# BOARD1_V2.net
KiCad netlist of a schematic drawn in Altium Designer
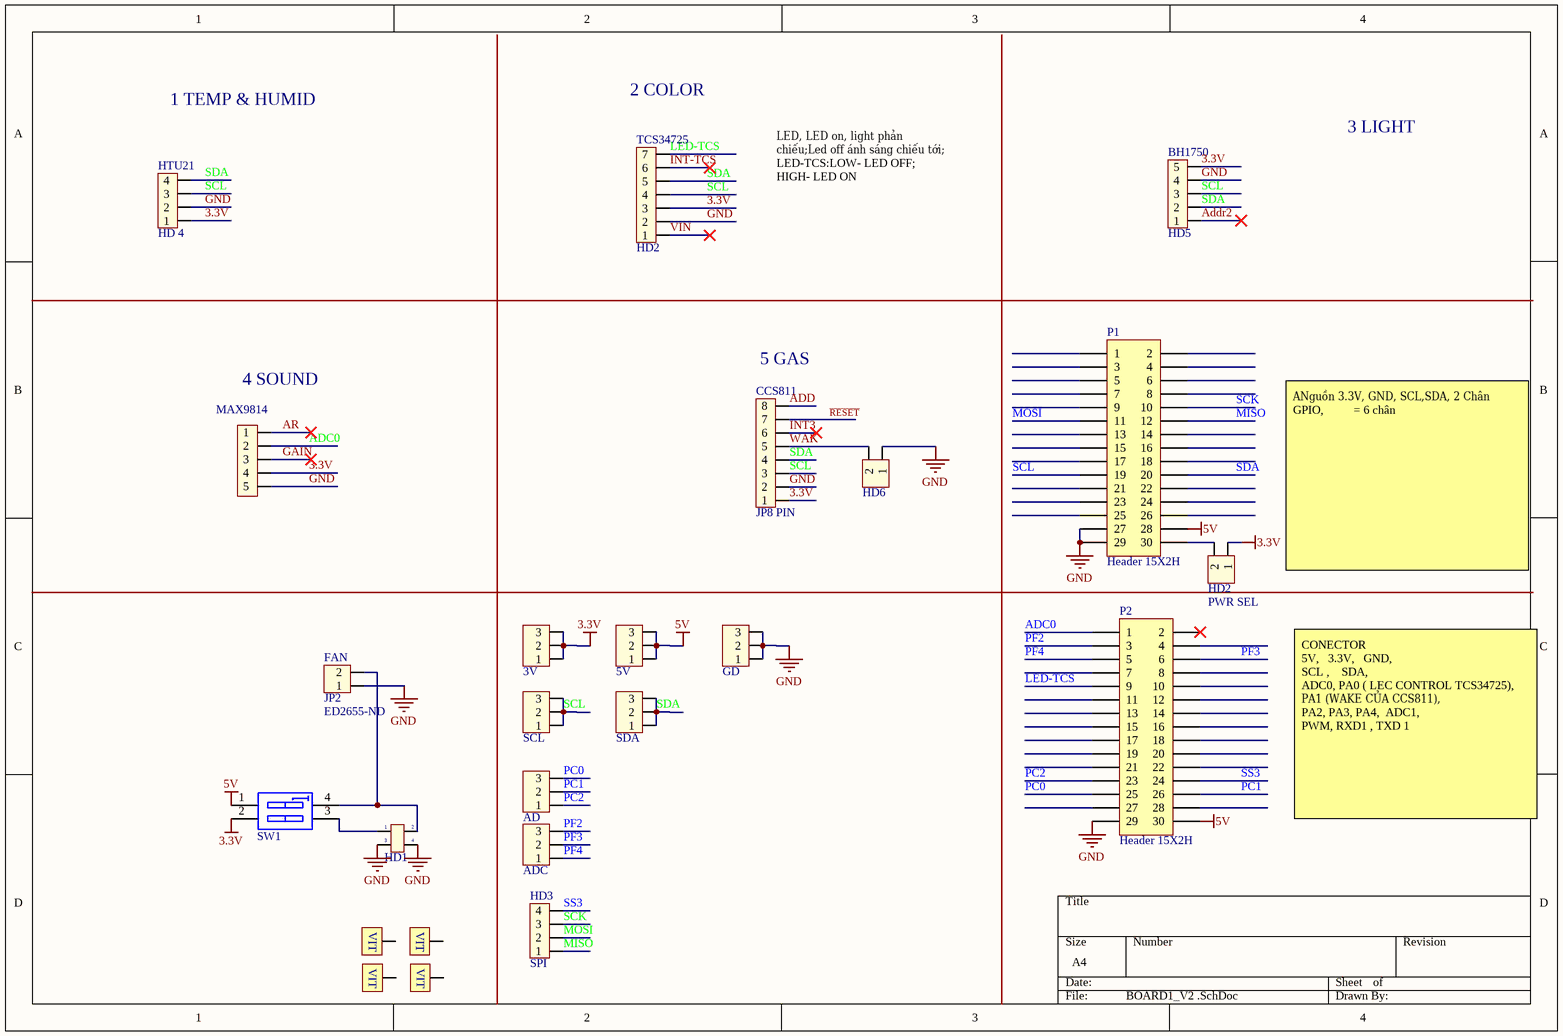
[diagram p0: BOARD1_V2 .SchDoc]

(export (version "E")
  (design (tool "Eeschema 10.0.6"))
  (components
    (comp (ref "3V") (value "Header 3") (footprint "Header_3") (libsource (lib "lpson") (part "Header3")))
    (comp (ref "5V") (value "Header 3") (footprint "Header_3") (libsource (lib "lpson") (part "Header3")))
    (comp (ref "AD") (value "Header 3") (footprint "Header_3") (libsource (lib "lpson") (part "Header3")))
    (comp (ref "ADC") (value "Header 3") (footprint "Header_3") (libsource (lib "lpson") (part "Header3")))
    (comp (ref "BH1750")
      (value "HD5")
      (footprint "BH1750")
      (description "Header 5")
      (fields (field (name "CREAT BY") "VanDungEvn@Gmail.com"))
      (libsource (lib "lpson") (part "Header5"))
    )
    (comp (ref "CCS811") (value "JP8 PIN") (footprint "CCS811V2") (libsource (lib "lpson") (part "JP8")))
    (comp (ref "FAN")
      (value "JP2")
      (footprint "CON2")
      (description "Terminal 2pin 5mm")
      (fields
        (field (name "MANUFACTURER") "On Shore Technology Inc.")
        (field (name "MANUFACTURER PART NUMBER") "OSTTH020160")
        (field (name "SUPPLIER PART NUMBER 1") "ED2655-ND")
      )
      (libsource (lib "lpson") (part "Terminal 2"))
    )
    (comp (ref "GD") (value "Header 3") (footprint "Header_3") (libsource (lib "lpson") (part "Header3")))
    (comp (ref "HD1") (value "Jumper 2x2") (footprint "HDR2X2") (libsource (lib "lpson") (part "JP2x2")))
    (comp (ref "HD2")
      (value "PWR SEL")
      (footprint "Header_2")
      (description "Header 2")
      (libsource (lib "lpson") (part "Header2"))
    )
    (comp (ref "HD3")
      (value "SPI")
      (footprint "Header_4")
      (description "Header 4")
      (libsource (lib "lpson") (part "Header4"))
    )
    (comp (ref "HD6")
      (value "PWR SEL")
      (footprint "Header_2")
      (description "Header 2")
      (libsource (lib "lpson") (part "Header2"))
    )
    (comp (ref "HTU21")
      (value "HD 4")
      (footprint "HTU-D")
      (description "Header 4")
      (libsource (lib "lpson") (part "Header4"))
    )
    (comp (ref "MAX9814")
      (value "JP5")
      (footprint "MAX9814")
      (libsource (lib "quangnguyen_lib_altium") (part "JP5"))
    )
    (comp (ref "P1")
      (value "Header 15X2H")
      (footprint "HED15X2H")
      (description "Header, 15-Pin, Dual row, Right Angle")
      (fields (field (name "PUBLISHER") "Altium Limited"))
      (libsource (lib "My Library") (part "Header 15X2H"))
    )
    (comp (ref "P2")
      (value "Header 15X2H")
      (footprint "HED15X2H")
      (description "Header, 15-Pin, Dual row, Right Angle")
      (fields (field (name "PUBLISHER") "Altium Limited"))
      (libsource (lib "My Library") (part "Header 15X2H"))
    )
    (comp (ref "SCL") (value "Header 3") (footprint "Header_3") (libsource (lib "lpson") (part "Header3")))
    (comp (ref "SDA") (value "Header 3") (footprint "Header_3") (libsource (lib "lpson") (part "Header3")))
    (comp (ref "SW1")
      (value "SW - DIP2")
      (footprint "DIP_Switch2")
      (description "DIP Switch, 2 Position, SPST")
      (libsource (lib "lpson") (part "SWDIP-2"))
    )
    (comp (ref "TCS34725")
      (value "HD2")
      (footprint "TCS34725V2")
      (description "JP7 PIN")
      (libsource (lib "lpson") (part "JP7"))
    )
    (comp (ref "VIT2")
      (value "1")
      (footprint "Screw 3 small")
      (description "Oc Vit")
      (libsource (lib "quangnguyen_lib_altium") (part "VIT"))
    )
    (comp (ref "VIT3")
      (value "1")
      (footprint "Screw 3 small")
      (description "Oc Vit")
      (libsource (lib "quangnguyen_lib_altium") (part "VIT"))
    )
    (comp (ref "VIT5")
      (value "1")
      (footprint "Screw 3 small")
      (description "Oc Vit")
      (libsource (lib "quangnguyen_lib_altium") (part "VIT"))
    )
    (comp (ref "VIT6")
      (value "1")
      (footprint "Screw 3 small")
      (description "Oc Vit")
      (libsource (lib "quangnguyen_lib_altium") (part "VIT"))
    )
  )
  (nets
    (net (code "1") (name "/ADC0") (class "Default")
      (node (ref "MAX9814") (pin "2") (pinfunction "2_2") (pintype "passive"))
      (node (ref "P2") (pin "1") (pinfunction "1_1") (pintype "passive"))
    )
    (net (code "2") (name "/ADD") (class "Default")
      (node (ref "CCS811") (pin "8") (pinfunction "8_8") (pintype "passive"))
    )
    (net (code "3") (name "/AR") (class "Default")
      (node (ref "MAX9814") (pin "1") (pinfunction "1_1") (pintype "passive+no_connect"))
    )
    (net (code "4") (name "/Addr2") (class "Default")
      (node (ref "BH1750") (pin "1") (pinfunction "1_1") (pintype "passive+no_connect"))
    )
    (net (code "5") (name "/GAIN") (class "Default")
      (node (ref "MAX9814") (pin "3") (pinfunction "3_3") (pintype "passive+no_connect"))
    )
    (net (code "6") (name "/INT-TCS") (class "Default")
      (node (ref "TCS34725") (pin "6") (pinfunction "6_6") (pintype "passive+no_connect"))
    )
    (net (code "7") (name "/INT3") (class "Default")
      (node (ref "CCS811") (pin "6") (pinfunction "6_6") (pintype "passive+no_connect"))
    )
    (net (code "8") (name "/LED-TCS") (class "Default")
      (node (ref "P2") (pin "9") (pinfunction "9_9") (pintype "passive"))
      (node (ref "TCS34725") (pin "7") (pinfunction "7_7") (pintype "passive"))
    )
    (net (code "9") (name "/MISO") (class "Default")
      (node (ref "HD3") (pin "1") (pinfunction "1_1") (pintype "passive"))
      (node (ref "P1") (pin "12") (pinfunction "12_12") (pintype "passive"))
    )
    (net (code "10") (name "/MOSI") (class "Default")
      (node (ref "HD3") (pin "2") (pinfunction "2_2") (pintype "passive"))
      (node (ref "P1") (pin "11") (pinfunction "11_11") (pintype "passive"))
    )
    (net (code "11") (name "/PC0") (class "Default")
      (node (ref "AD") (pin "3") (pinfunction "3_3") (pintype "passive"))
      (node (ref "P2") (pin "25") (pinfunction "25_25") (pintype "passive"))
    )
    (net (code "12") (name "/PC1") (class "Default")
      (node (ref "AD") (pin "2") (pinfunction "2_2") (pintype "passive"))
      (node (ref "P2") (pin "26") (pinfunction "26_26") (pintype "passive"))
    )
    (net (code "13") (name "/PC2") (class "Default")
      (node (ref "AD") (pin "1") (pinfunction "1_1") (pintype "passive"))
      (node (ref "P2") (pin "23") (pinfunction "23_23") (pintype "passive"))
    )
    (net (code "14") (name "/PF2") (class "Default")
      (node (ref "ADC") (pin "3") (pinfunction "3_3") (pintype "passive"))
      (node (ref "P2") (pin "3") (pinfunction "3_3") (pintype "passive"))
    )
    (net (code "15") (name "/PF3") (class "Default")
      (node (ref "ADC") (pin "2") (pinfunction "2_2") (pintype "passive"))
      (node (ref "P2") (pin "6") (pinfunction "6_6") (pintype "passive"))
    )
    (net (code "16") (name "/PF4") (class "Default")
      (node (ref "ADC") (pin "1") (pinfunction "1_1") (pintype "passive"))
      (node (ref "P2") (pin "5") (pinfunction "5_5") (pintype "passive"))
    )
    (net (code "17") (name "/SCK") (class "Default")
      (node (ref "HD3") (pin "3") (pinfunction "3_3") (pintype "passive"))
      (node (ref "P1") (pin "10") (pinfunction "10_10") (pintype "passive"))
    )
    (net (code "18") (name "/SCL") (class "Default")
      (node (ref "BH1750") (pin "3") (pinfunction "3_3") (pintype "passive"))
      (node (ref "CCS811") (pin "3") (pinfunction "3_3") (pintype "passive"))
      (node (ref "HTU21") (pin "3") (pinfunction "3_3") (pintype "passive"))
      (node (ref "P1") (pin "19") (pinfunction "19_19") (pintype "passive"))
      (node (ref "SCL") (pin "1") (pinfunction "1_1") (pintype "passive"))
      (node (ref "SCL") (pin "2") (pinfunction "2_2") (pintype "passive"))
      (node (ref "SCL") (pin "3") (pinfunction "3_3") (pintype "passive"))
      (node (ref "TCS34725") (pin "4") (pinfunction "4_4") (pintype "passive"))
    )
    (net (code "19") (name "/SDA") (class "Default")
      (node (ref "BH1750") (pin "2") (pinfunction "2_2") (pintype "passive"))
      (node (ref "CCS811") (pin "4") (pinfunction "4_4") (pintype "passive"))
      (node (ref "HTU21") (pin "4") (pinfunction "4_4") (pintype "passive"))
      (node (ref "P1") (pin "20") (pinfunction "20_20") (pintype "passive"))
      (node (ref "SDA") (pin "1") (pinfunction "1_1") (pintype "passive"))
      (node (ref "SDA") (pin "2") (pinfunction "2_2") (pintype "passive"))
      (node (ref "SDA") (pin "3") (pinfunction "3_3") (pintype "passive"))
      (node (ref "TCS34725") (pin "5") (pinfunction "5_5") (pintype "passive"))
    )
    (net (code "20") (name "/SS3") (class "Default")
      (node (ref "HD3") (pin "4") (pinfunction "4_4") (pintype "passive"))
      (node (ref "P2") (pin "24") (pinfunction "24_24") (pintype "passive"))
    )
    (net (code "21") (name "/VIN") (class "Default")
      (node (ref "TCS34725") (pin "1") (pinfunction "1_1") (pintype "passive+no_connect"))
    )
    (net (code "22") (name "/WAK") (class "Default")
      (node (ref "CCS811") (pin "5") (pinfunction "5_5") (pintype "passive"))
      (node (ref "HD6") (pin "2") (pinfunction "2_2") (pintype "passive"))
    )
    (net (code "23") (name "/~{RESET}") (class "Default")
      (node (ref "CCS811") (pin "7") (pinfunction "7_7") (pintype "passive"))
    )
    (net (code "24") (name "3.3V") (class "Default")
      (node (ref "3V") (pin "1") (pinfunction "1_1") (pintype "passive"))
      (node (ref "3V") (pin "2") (pinfunction "2_2") (pintype "passive"))
      (node (ref "3V") (pin "3") (pinfunction "3_3") (pintype "passive"))
      (node (ref "BH1750") (pin "5") (pinfunction "5_5") (pintype "passive"))
      (node (ref "CCS811") (pin "1") (pinfunction "1_1") (pintype "passive"))
      (node (ref "HD2") (pin "1") (pinfunction "1_1") (pintype "passive"))
      (node (ref "HTU21") (pin "1") (pinfunction "1_1") (pintype "passive"))
      (node (ref "MAX9814") (pin "4") (pinfunction "4_4") (pintype "passive"))
      (node (ref "SW1") (pin "2") (pinfunction "A2_2") (pintype "passive"))
      (node (ref "TCS34725") (pin "3") (pinfunction "3_3") (pintype "passive"))
    )
    (net (code "25") (name "5V") (class "Default")
      (node (ref "5V") (pin "1") (pinfunction "1_1") (pintype "passive"))
      (node (ref "5V") (pin "2") (pinfunction "2_2") (pintype "passive"))
      (node (ref "5V") (pin "3") (pinfunction "3_3") (pintype "passive"))
      (node (ref "P1") (pin "28") (pinfunction "28_28") (pintype "passive"))
      (node (ref "P2") (pin "30") (pinfunction "30_30") (pintype "passive"))
      (node (ref "SW1") (pin "1") (pinfunction "A1_1") (pintype "passive"))
    )
    (net (code "26") (name "GND") (class "Default")
      (node (ref "BH1750") (pin "4") (pinfunction "4_4") (pintype "passive"))
      (node (ref "CCS811") (pin "2") (pinfunction "2_2") (pintype "passive"))
      (node (ref "FAN") (pin "1") (pinfunction "1_1") (pintype "passive"))
      (node (ref "GD") (pin "1") (pinfunction "1_1") (pintype "passive"))
      (node (ref "GD") (pin "2") (pinfunction "2_2") (pintype "passive"))
      (node (ref "GD") (pin "3") (pinfunction "3_3") (pintype "passive"))
      (node (ref "HD1") (pin "3") (pinfunction "3_3") (pintype "passive"))
      (node (ref "HD1") (pin "4") (pinfunction "4_4") (pintype "passive"))
      (node (ref "HD6") (pin "1") (pinfunction "1_1") (pintype "passive"))
      (node (ref "HTU21") (pin "2") (pinfunction "2_2") (pintype "passive"))
      (node (ref "MAX9814") (pin "5") (pinfunction "5_5") (pintype "passive"))
      (node (ref "P1") (pin "27") (pinfunction "27_27") (pintype "passive"))
      (node (ref "P1") (pin "29") (pinfunction "29_29") (pintype "passive"))
      (node (ref "P2") (pin "29") (pinfunction "29_29") (pintype "passive"))
      (node (ref "TCS34725") (pin "2") (pinfunction "2_2") (pintype "passive"))
    )
    (net (code "27") (name "Net-(HD2-Pad2)") (class "Default")
      (node (ref "HD2") (pin "2") (pinfunction "2_2") (pintype "passive"))
      (node (ref "P1") (pin "30") (pinfunction "30_30") (pintype "passive"))
    )
    (net (code "28") (name "Net-(SW1-A3)") (class "Default")
      (node (ref "HD1") (pin "1") (pinfunction "1_1") (pintype "passive"))
      (node (ref "SW1") (pin "3") (pinfunction "A3_3") (pintype "passive"))
    )
    (net (code "29") (name "Net-(SW1-A4)") (class "Default")
      (node (ref "FAN") (pin "2") (pinfunction "2_2") (pintype "passive"))
      (node (ref "HD1") (pin "2") (pinfunction "2_2") (pintype "passive"))
      (node (ref "SW1") (pin "4") (pinfunction "A4_4") (pintype "passive"))
    )
    (net (code "30") (name "unconnected-(P1-Pad1)") (class "Default")
      (node (ref "P1") (pin "1") (pinfunction "1_1") (pintype "passive"))
    )
    (net (code "31") (name "unconnected-(P1-Pad2)") (class "Default")
      (node (ref "P1") (pin "2") (pinfunction "2_2") (pintype "passive"))
    )
    (net (code "32") (name "unconnected-(P1-Pad3)") (class "Default")
      (node (ref "P1") (pin "3") (pinfunction "3_3") (pintype "passive"))
    )
    (net (code "33") (name "unconnected-(P1-Pad4)") (class "Default")
      (node (ref "P1") (pin "4") (pinfunction "4_4") (pintype "passive"))
    )
    (net (code "34") (name "unconnected-(P1-Pad5)") (class "Default")
      (node (ref "P1") (pin "5") (pinfunction "5_5") (pintype "passive"))
    )
    (net (code "35") (name "unconnected-(P1-Pad6)") (class "Default")
      (node (ref "P1") (pin "6") (pinfunction "6_6") (pintype "passive"))
    )
    (net (code "36") (name "unconnected-(P1-Pad7)") (class "Default")
      (node (ref "P1") (pin "7") (pinfunction "7_7") (pintype "passive"))
    )
    (net (code "37") (name "unconnected-(P1-Pad8)") (class "Default")
      (node (ref "P1") (pin "8") (pinfunction "8_8") (pintype "passive"))
    )
    (net (code "38") (name "unconnected-(P1-Pad9)") (class "Default")
      (node (ref "P1") (pin "9") (pinfunction "9_9") (pintype "passive"))
    )
    (net (code "39") (name "unconnected-(P1-Pad13)") (class "Default")
      (node (ref "P1") (pin "13") (pinfunction "13_13") (pintype "passive"))
    )
    (net (code "40") (name "unconnected-(P1-Pad14)") (class "Default")
      (node (ref "P1") (pin "14") (pinfunction "14_14") (pintype "passive"))
    )
    (net (code "41") (name "unconnected-(P1-Pad15)") (class "Default")
      (node (ref "P1") (pin "15") (pinfunction "15_15") (pintype "passive"))
    )
    (net (code "42") (name "unconnected-(P1-Pad16)") (class "Default")
      (node (ref "P1") (pin "16") (pinfunction "16_16") (pintype "passive"))
    )
    (net (code "43") (name "unconnected-(P1-Pad17)") (class "Default")
      (node (ref "P1") (pin "17") (pinfunction "17_17") (pintype "passive"))
    )
    (net (code "44") (name "unconnected-(P1-Pad18)") (class "Default")
      (node (ref "P1") (pin "18") (pinfunction "18_18") (pintype "passive"))
    )
    (net (code "45") (name "unconnected-(P1-Pad21)") (class "Default")
      (node (ref "P1") (pin "21") (pinfunction "21_21") (pintype "passive"))
    )
    (net (code "46") (name "unconnected-(P1-Pad22)") (class "Default")
      (node (ref "P1") (pin "22") (pinfunction "22_22") (pintype "passive"))
    )
    (net (code "47") (name "unconnected-(P1-Pad23)") (class "Default")
      (node (ref "P1") (pin "23") (pinfunction "23_23") (pintype "passive"))
    )
    (net (code "48") (name "unconnected-(P1-Pad24)") (class "Default")
      (node (ref "P1") (pin "24") (pinfunction "24_24") (pintype "passive"))
    )
    (net (code "49") (name "unconnected-(P1-Pad25)") (class "Default")
      (node (ref "P1") (pin "25") (pinfunction "25_25") (pintype "passive"))
    )
    (net (code "50") (name "unconnected-(P1-Pad26)") (class "Default")
      (node (ref "P1") (pin "26") (pinfunction "26_26") (pintype "passive"))
    )
    (net (code "51") (name "unconnected-(P2-Pad2)") (class "Default")
      (node (ref "P2") (pin "2") (pinfunction "2_2") (pintype "passive+no_connect"))
    )
    (net (code "52") (name "unconnected-(P2-Pad4)") (class "Default")
      (node (ref "P2") (pin "4") (pinfunction "4_4") (pintype "passive"))
    )
    (net (code "53") (name "unconnected-(P2-Pad7)") (class "Default")
      (node (ref "P2") (pin "7") (pinfunction "7_7") (pintype "passive"))
    )
    (net (code "54") (name "unconnected-(P2-Pad8)") (class "Default")
      (node (ref "P2") (pin "8") (pinfunction "8_8") (pintype "passive"))
    )
    (net (code "55") (name "unconnected-(P2-Pad10)") (class "Default")
      (node (ref "P2") (pin "10") (pinfunction "10_10") (pintype "passive"))
    )
    (net (code "56") (name "unconnected-(P2-Pad11)") (class "Default")
      (node (ref "P2") (pin "11") (pinfunction "11_11") (pintype "passive"))
    )
    (net (code "57") (name "unconnected-(P2-Pad12)") (class "Default")
      (node (ref "P2") (pin "12") (pinfunction "12_12") (pintype "passive"))
    )
    (net (code "58") (name "unconnected-(P2-Pad13)") (class "Default")
      (node (ref "P2") (pin "13") (pinfunction "13_13") (pintype "passive"))
    )
    (net (code "59") (name "unconnected-(P2-Pad14)") (class "Default")
      (node (ref "P2") (pin "14") (pinfunction "14_14") (pintype "passive"))
    )
    (net (code "60") (name "unconnected-(P2-Pad15)") (class "Default")
      (node (ref "P2") (pin "15") (pinfunction "15_15") (pintype "passive"))
    )
    (net (code "61") (name "unconnected-(P2-Pad16)") (class "Default")
      (node (ref "P2") (pin "16") (pinfunction "16_16") (pintype "passive"))
    )
    (net (code "62") (name "unconnected-(P2-Pad17)") (class "Default")
      (node (ref "P2") (pin "17") (pinfunction "17_17") (pintype "passive"))
    )
    (net (code "63") (name "unconnected-(P2-Pad18)") (class "Default")
      (node (ref "P2") (pin "18") (pinfunction "18_18") (pintype "passive"))
    )
    (net (code "64") (name "unconnected-(P2-Pad19)") (class "Default")
      (node (ref "P2") (pin "19") (pinfunction "19_19") (pintype "passive"))
    )
    (net (code "65") (name "unconnected-(P2-Pad20)") (class "Default")
      (node (ref "P2") (pin "20") (pinfunction "20_20") (pintype "passive"))
    )
    (net (code "66") (name "unconnected-(P2-Pad21)") (class "Default")
      (node (ref "P2") (pin "21") (pinfunction "21_21") (pintype "passive"))
    )
    (net (code "67") (name "unconnected-(P2-Pad22)") (class "Default")
      (node (ref "P2") (pin "22") (pinfunction "22_22") (pintype "passive"))
    )
    (net (code "68") (name "unconnected-(P2-Pad27)") (class "Default")
      (node (ref "P2") (pin "27") (pinfunction "27_27") (pintype "passive"))
    )
    (net (code "69") (name "unconnected-(P2-Pad28)") (class "Default")
      (node (ref "P2") (pin "28") (pinfunction "28_28") (pintype "passive"))
    )
    (net (code "70") (name "unconnected-(VIT2-1-PadVIT1)") (class "Default")
      (node (ref "VIT2") (pin "VIT1") (pinfunction "1_VIT1") (pintype "passive"))
    )
    (net (code "71") (name "unconnected-(VIT3-1-PadVIT1)") (class "Default")
      (node (ref "VIT3") (pin "VIT1") (pinfunction "1_VIT1") (pintype "passive"))
    )
    (net (code "72") (name "unconnected-(VIT5-1-PadVIT1)") (class "Default")
      (node (ref "VIT5") (pin "VIT1") (pinfunction "1_VIT1") (pintype "passive"))
    )
    (net (code "73") (name "unconnected-(VIT6-1-PadVIT1)") (class "Default")
      (node (ref "VIT6") (pin "VIT1") (pinfunction "1_VIT1") (pintype "passive"))
    )
  )
)
